# irisc.net
KiCad netlist of a schematic drawn in EAGLE
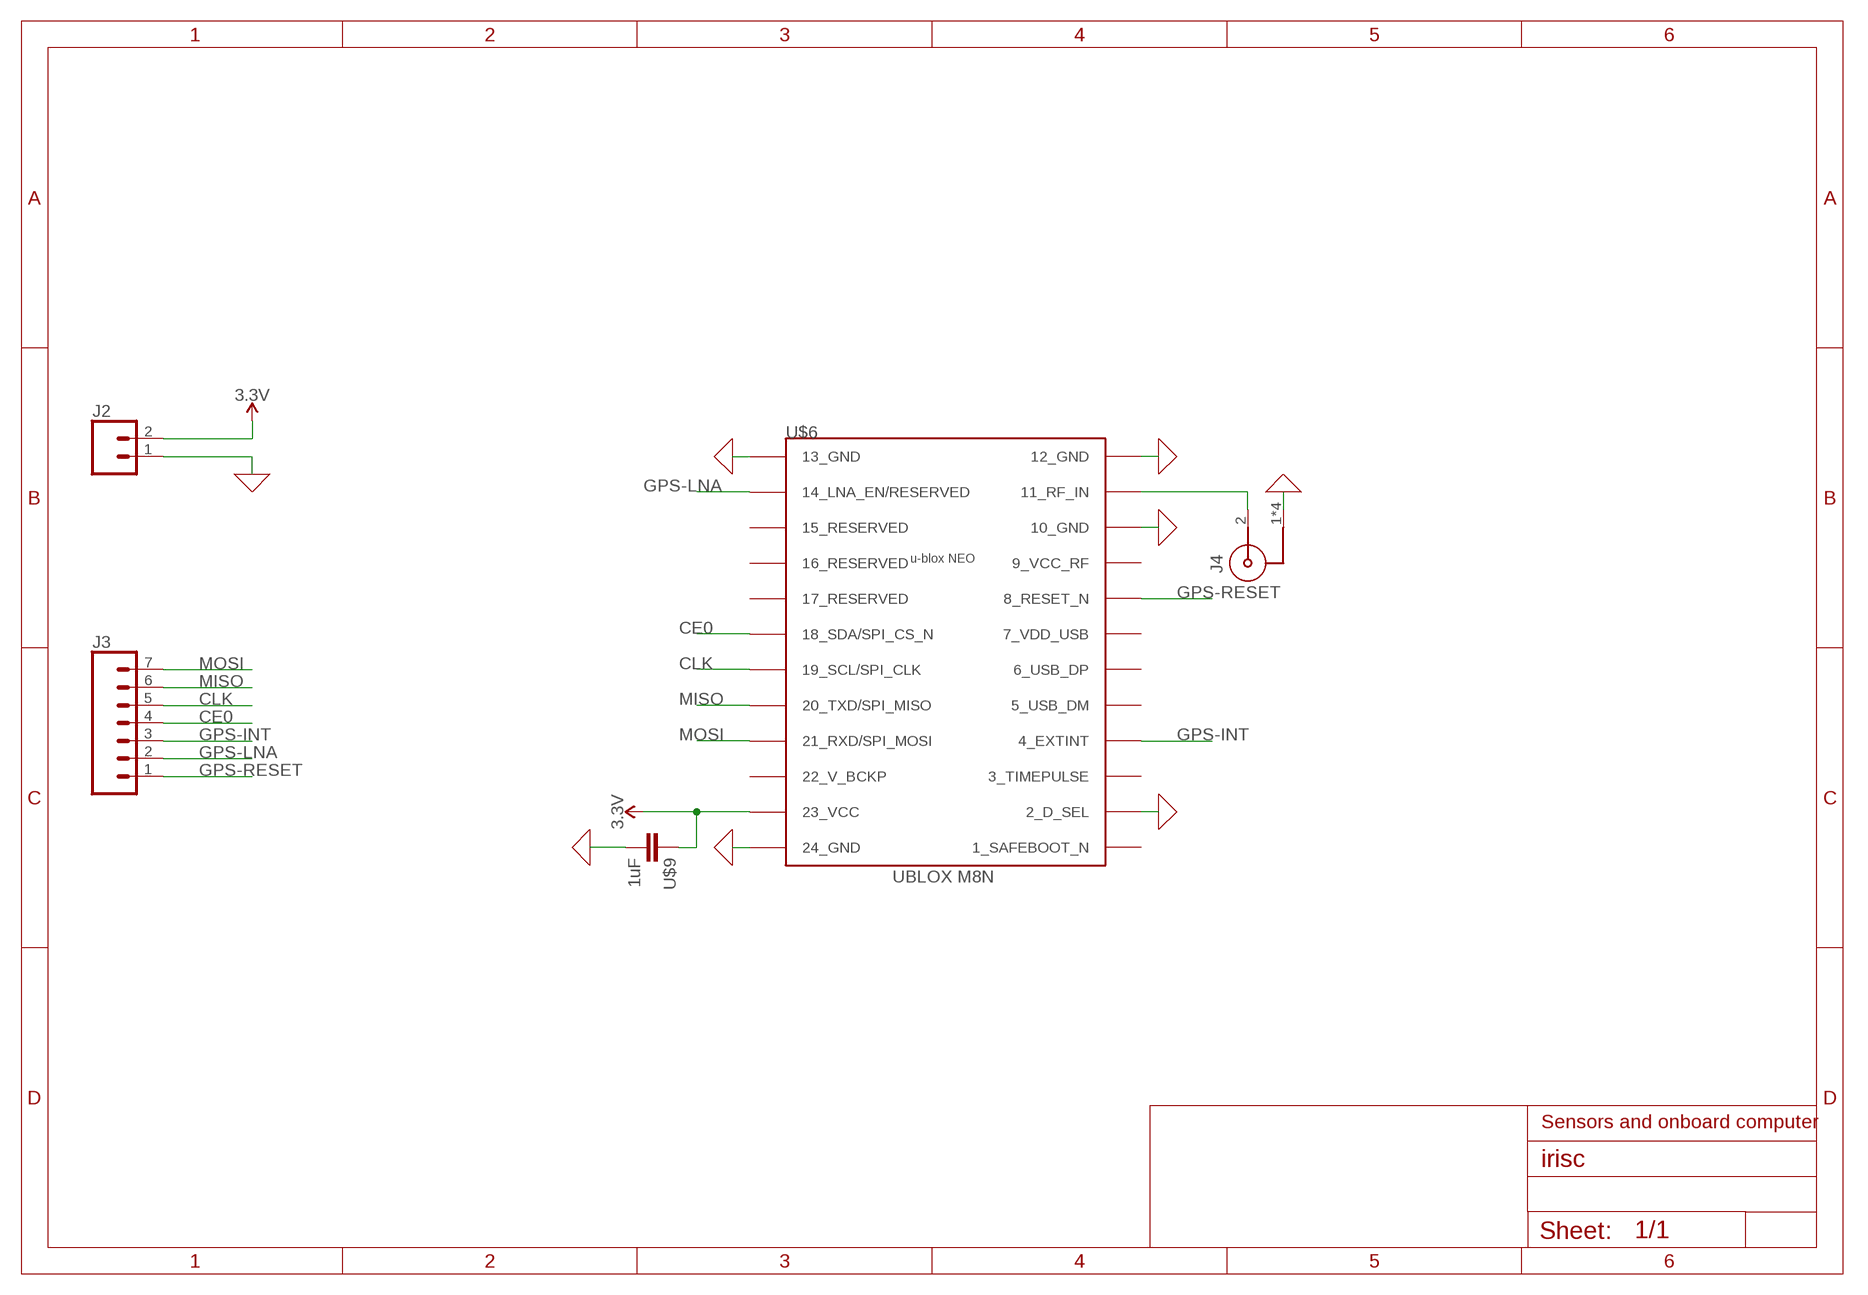
[diagram p0: schematic, sheet 1]

(export (version "E")
  (design (tool "Eeschema 10.0.6"))
  (components
    (comp (ref "J2")
      (value "CONN_02")
      (footprint "eagle-import:1X02")
      (libsource (lib "eagle-import") (part "CONN_02"))
    )
    (comp (ref "J3")
      (value "CONN_07")
      (footprint "eagle-import:1X07")
      (libsource (lib "eagle-import") (part "CONN_07"))
    )
    (comp (ref "J4")
      (value "60312202114508")
      (footprint "eagle-import:60312202114508")
      (libsource (lib "eagle-import") (part "60312202114508"))
    )
    (comp (ref "U$6")
      (value "NEO-M8")
      (footprint "eagle-import:NEO-M8")
      (libsource (lib "eagle-import") (part "NEO-M8"))
    )
    (comp (ref "U$9")
      (value "1uF")
      (footprint "eagle-import:RESC0603_N")
      (libsource (lib "eagle-import") (part "CAPACITOR_0603_N"))
    )
  )
  (nets
    (net (code "1") (name "/CE0") (class "Default")
      (node (ref "J3") (pin "4") (pinfunction "4_4") (pintype "passive"))
      (node (ref "U$6") (pin "18") (pinfunction "18_SDA/SPI_CS_N_18") (pintype "bidirectional"))
    )
    (net (code "2") (name "/CLK") (class "Default")
      (node (ref "J3") (pin "5") (pinfunction "5_5") (pintype "passive"))
      (node (ref "U$6") (pin "19") (pinfunction "19_SCL/SPI_CLK_19") (pintype "bidirectional"))
    )
    (net (code "3") (name "/GPS-INT") (class "Default")
      (node (ref "J3") (pin "3") (pinfunction "3_3") (pintype "passive"))
      (node (ref "U$6") (pin "4") (pinfunction "4_EXTINT_4") (pintype "bidirectional"))
    )
    (net (code "4") (name "/GPS-LNA") (class "Default")
      (node (ref "J3") (pin "2") (pinfunction "2_2") (pintype "passive"))
      (node (ref "U$6") (pin "14") (pinfunction "14_LNA_EN/RESERVED_14") (pintype "bidirectional"))
    )
    (net (code "5") (name "/GPS-RESET") (class "Default")
      (node (ref "J3") (pin "1") (pinfunction "1_1") (pintype "passive"))
      (node (ref "U$6") (pin "8") (pinfunction "8_RESET_N_8") (pintype "bidirectional"))
    )
    (net (code "6") (name "/MISO") (class "Default")
      (node (ref "J3") (pin "6") (pinfunction "6_6") (pintype "passive"))
      (node (ref "U$6") (pin "20") (pinfunction "20_TXD/SPI_MISO_20") (pintype "bidirectional"))
    )
    (net (code "7") (name "/MOSI") (class "Default")
      (node (ref "J3") (pin "7") (pinfunction "7_7") (pintype "passive"))
      (node (ref "U$6") (pin "21") (pinfunction "21_RXD/SPI_MOSI_21") (pintype "bidirectional"))
    )
    (net (code "8") (name "3.3V") (class "Default")
      (node (ref "J2") (pin "2") (pinfunction "2_2") (pintype "passive"))
      (node (ref "U$6") (pin "23") (pinfunction "23_VCC_23") (pintype "bidirectional"))
      (node (ref "U$9") (pin "1") (pinfunction "1_1") (pintype "passive"))
    )
    (net (code "9") (name "GND") (class "Default")
      (node (ref "J2") (pin "1") (pinfunction "1_1") (pintype "passive"))
      (node (ref "J4") (pin "1") (pinfunction "2_1") (pintype "passive"))
      (node (ref "J4") (pin "3") (pinfunction "2_3") (pintype "passive"))
      (node (ref "J4") (pin "4") (pinfunction "2_4") (pintype "passive"))
      (node (ref "J4") (pin "5") (pinfunction "2_5") (pintype "passive"))
      (node (ref "U$6") (pin "10") (pinfunction "10_GND_10") (pintype "bidirectional"))
      (node (ref "U$6") (pin "12") (pinfunction "12_GND_12") (pintype "bidirectional"))
      (node (ref "U$6") (pin "13") (pinfunction "13_GND_13") (pintype "bidirectional"))
      (node (ref "U$6") (pin "2") (pinfunction "2_D_SEL_2") (pintype "bidirectional"))
      (node (ref "U$6") (pin "24") (pinfunction "24_GND_24") (pintype "bidirectional"))
      (node (ref "U$9") (pin "2") (pinfunction "2_2") (pintype "passive"))
    )
    (net (code "10") (name "Net-(J4-1)") (class "Default")
      (node (ref "J4") (pin "2") (pinfunction "1_2") (pintype "passive"))
      (node (ref "U$6") (pin "11") (pinfunction "11_RF_IN_11") (pintype "bidirectional"))
    )
    (net (code "11") (name "unconnected-(U$6-1_SAFEBOOT_N-Pad1)") (class "Default")
      (node (ref "U$6") (pin "1") (pinfunction "1_SAFEBOOT_N_1") (pintype "bidirectional"))
    )
    (net (code "12") (name "unconnected-(U$6-3_TIMEPULSE-Pad3)") (class "Default")
      (node (ref "U$6") (pin "3") (pinfunction "3_TIMEPULSE_3") (pintype "bidirectional"))
    )
    (net (code "13") (name "unconnected-(U$6-5_USB_DM-Pad5)") (class "Default")
      (node (ref "U$6") (pin "5") (pinfunction "5_USB_DM_5") (pintype "bidirectional"))
    )
    (net (code "14") (name "unconnected-(U$6-6_USB_DP-Pad6)") (class "Default")
      (node (ref "U$6") (pin "6") (pinfunction "6_USB_DP_6") (pintype "bidirectional"))
    )
    (net (code "15") (name "unconnected-(U$6-7_VDD_USB-Pad7)") (class "Default")
      (node (ref "U$6") (pin "7") (pinfunction "7_VDD_USB_7") (pintype "bidirectional"))
    )
    (net (code "16") (name "unconnected-(U$6-9_VCC_RF-Pad9)") (class "Default")
      (node (ref "U$6") (pin "9") (pinfunction "9_VCC_RF_9") (pintype "bidirectional"))
    )
    (net (code "17") (name "unconnected-(U$6-15_RESERVED-Pad15)") (class "Default")
      (node (ref "U$6") (pin "15") (pinfunction "15_RESERVED_15") (pintype "bidirectional"))
    )
    (net (code "18") (name "unconnected-(U$6-16_RESERVED-Pad16)") (class "Default")
      (node (ref "U$6") (pin "16") (pinfunction "16_RESERVED_16") (pintype "bidirectional"))
    )
    (net (code "19") (name "unconnected-(U$6-17_RESERVED-Pad17)") (class "Default")
      (node (ref "U$6") (pin "17") (pinfunction "17_RESERVED_17") (pintype "bidirectional"))
    )
    (net (code "20") (name "unconnected-(U$6-22_V_BCKP-Pad22)") (class "Default")
      (node (ref "U$6") (pin "22") (pinfunction "22_V_BCKP_22") (pintype "bidirectional"))
    )
  )
)
